# module.net
KiCad netlist of a schematic drawn in EAGLE
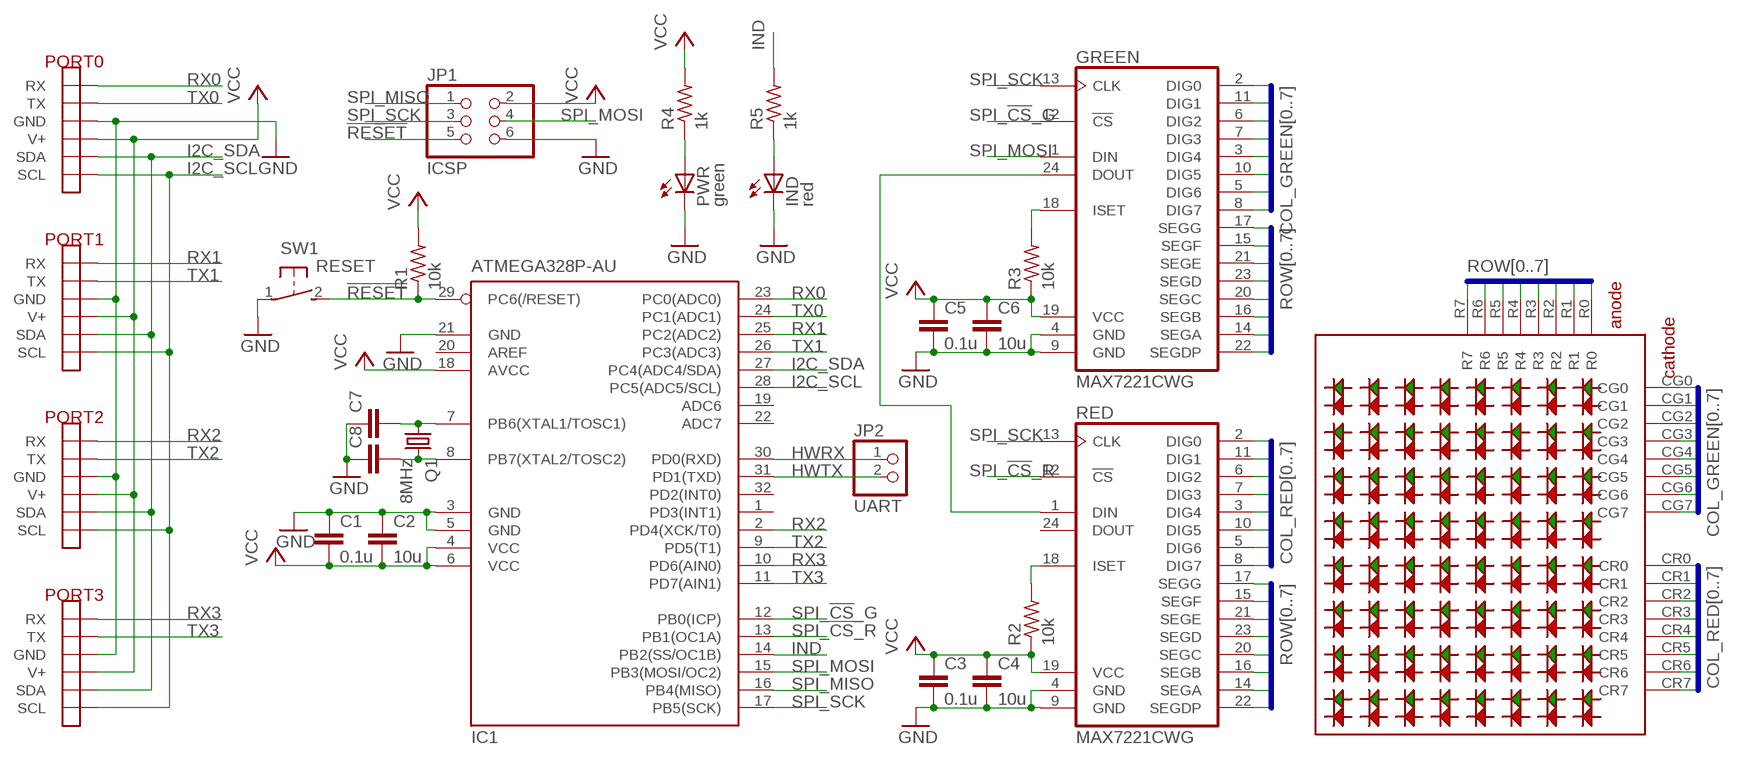
[diagram p0: schematic, sheet 1]

(export (version "E")
  (design (tool "Eeschema 10.0.6"))
  (components
    (comp (ref "C1")
      (value "0.1u")
      (footprint "eagle-import:C0805")
      (libsource (lib "eagle-import") (part "C-EUC0805"))
    )
    (comp (ref "C2")
      (value "10u")
      (footprint "eagle-import:C1206")
      (libsource (lib "eagle-import") (part "C-EUC1206"))
    )
    (comp (ref "C3")
      (value "0.1u")
      (footprint "eagle-import:C0805")
      (libsource (lib "eagle-import") (part "C-EUC0805"))
    )
    (comp (ref "C4")
      (value "10u")
      (footprint "eagle-import:C1206")
      (libsource (lib "eagle-import") (part "C-EUC1206"))
    )
    (comp (ref "C5")
      (value "0.1u")
      (footprint "eagle-import:C0805")
      (libsource (lib "eagle-import") (part "C-EUC0805"))
    )
    (comp (ref "C6")
      (value "10u")
      (footprint "eagle-import:C1206")
      (libsource (lib "eagle-import") (part "C-EUC1206"))
    )
    (comp (ref "C7")
      (value "C-EUC0805")
      (footprint "eagle-import:C0805")
      (libsource (lib "eagle-import") (part "C-EUC0805"))
    )
    (comp (ref "C8")
      (value "C-EUC0805")
      (footprint "eagle-import:C0805")
      (libsource (lib "eagle-import") (part "C-EUC0805"))
    )
    (comp (ref "GREEN")
      (value "MAX7221CWG")
      (footprint "eagle-import:SO24L")
      (fields (field (name "MF") "MAXIM"))
      (libsource (lib "eagle-import") (part "MAX7221CWG"))
    )
    (comp (ref "IC1")
      (value "ATMEGA328P-AU")
      (footprint "eagle-import:TQFP32-08")
      (fields (field (name "MF") "ATMEL"))
      (libsource (lib "eagle-import") (part "ATMEGA328P-AU"))
    )
    (comp (ref "IND")
      (value "red")
      (footprint "eagle-import:CHIPLED_0805")
      (libsource (lib "eagle-import") (part "LEDCHIPLED_0805"))
    )
    (comp (ref "JP1")
      (value "ICSP")
      (footprint "eagle-import:2X03")
      (libsource (lib "eagle-import") (part "PINHD-2X3"))
    )
    (comp (ref "JP2")
      (value "UART")
      (footprint "eagle-import:1X02")
      (libsource (lib "eagle-import") (part "PINHD-1X2"))
    )
    (comp (ref "PORT0")
      (value "PORT")
      (footprint "eagle-import:PORT")
      (libsource (lib "eagle-import") (part "PORT"))
    )
    (comp (ref "PORT1")
      (value "PORT")
      (footprint "eagle-import:PORT")
      (libsource (lib "eagle-import") (part "PORT"))
    )
    (comp (ref "PORT2")
      (value "PORT")
      (footprint "eagle-import:PORT")
      (libsource (lib "eagle-import") (part "PORT"))
    )
    (comp (ref "PORT3")
      (value "PORT")
      (footprint "eagle-import:PORT")
      (libsource (lib "eagle-import") (part "PORT"))
    )
    (comp (ref "PWR")
      (value "green")
      (footprint "eagle-import:CHIPLED_0805")
      (libsource (lib "eagle-import") (part "LEDCHIPLED_0805"))
    )
    (comp (ref "Q1")
      (value "8MHz")
      (footprint "eagle-import:HC49UP")
      (libsource (lib "eagle-import") (part "CRYSTALHC49UP"))
    )
    (comp (ref "R1")
      (value "10k")
      (footprint "eagle-import:R0805")
      (libsource (lib "eagle-import") (part "R-US_R0805"))
    )
    (comp (ref "R2")
      (value "10k")
      (footprint "eagle-import:R0805")
      (libsource (lib "eagle-import") (part "R-US_R0805"))
    )
    (comp (ref "R3")
      (value "10k")
      (footprint "eagle-import:R0805")
      (libsource (lib "eagle-import") (part "R-US_R0805"))
    )
    (comp (ref "R4")
      (value "1k")
      (footprint "eagle-import:R0805")
      (libsource (lib "eagle-import") (part "R-US_R0805"))
    )
    (comp (ref "R5")
      (value "1k")
      (footprint "eagle-import:R0805")
      (libsource (lib "eagle-import") (part "R-US_R0805"))
    )
    (comp (ref "RED")
      (value "MAX7221CWG")
      (footprint "eagle-import:SO24L")
      (fields (field (name "MF") "MAXIM"))
      (libsource (lib "eagle-import") (part "MAX7221CWG"))
    )
    (comp (ref "SW1")
      (value "RESET")
      (footprint "eagle-import:DTSM-3")
      (libsource (lib "eagle-import") (part "DTSM-3"))
    )
    (comp (ref "U$2")
      (value "88LED_MATRIX_BICOLOR_ROW_ANODE")
      (footprint "eagle-import:8_8LED_MATRIX_BICOLOR_ROW_ANODE")
      (libsource (lib "eagle-import") (part "88LED_MATRIX_BICOLOR_ROW_ANODE"))
    )
  )
  (nets
    (net (code "1") (name "/COL_GREEN0") (class "Default")
      (node (ref "GREEN") (pin "2") (pinfunction "DIG0_2") (pintype "output"))
      (node (ref "U$2") (pin "CG0") (pinfunction "CG0_CG0") (pintype "input"))
    )
    (net (code "2") (name "/COL_GREEN1") (class "Default")
      (node (ref "GREEN") (pin "11") (pinfunction "DIG1_11") (pintype "output"))
      (node (ref "U$2") (pin "CG1") (pinfunction "CG1_CG1") (pintype "input"))
    )
    (net (code "3") (name "/COL_GREEN2") (class "Default")
      (node (ref "GREEN") (pin "6") (pinfunction "DIG2_6") (pintype "output"))
      (node (ref "U$2") (pin "CG2") (pinfunction "CG2_CG2") (pintype "input"))
    )
    (net (code "4") (name "/COL_GREEN3") (class "Default")
      (node (ref "GREEN") (pin "7") (pinfunction "DIG3_7") (pintype "output"))
      (node (ref "U$2") (pin "CG3") (pinfunction "CG3_CG3") (pintype "input"))
    )
    (net (code "5") (name "/COL_GREEN4") (class "Default")
      (node (ref "GREEN") (pin "3") (pinfunction "DIG4_3") (pintype "output"))
      (node (ref "U$2") (pin "CG4") (pinfunction "CG4_CG4") (pintype "input"))
    )
    (net (code "6") (name "/COL_GREEN5") (class "Default")
      (node (ref "GREEN") (pin "10") (pinfunction "DIG5_10") (pintype "output"))
      (node (ref "U$2") (pin "CG5") (pinfunction "CG5_CG5") (pintype "input"))
    )
    (net (code "7") (name "/COL_GREEN6") (class "Default")
      (node (ref "GREEN") (pin "5") (pinfunction "DIG6_5") (pintype "output"))
      (node (ref "U$2") (pin "CG6") (pinfunction "CG6_CG6") (pintype "input"))
    )
    (net (code "8") (name "/COL_GREEN7") (class "Default")
      (node (ref "GREEN") (pin "8") (pinfunction "DIG7_8") (pintype "output"))
      (node (ref "U$2") (pin "CG7") (pinfunction "CG7_CG7") (pintype "input"))
    )
    (net (code "9") (name "/COL_RED0") (class "Default")
      (node (ref "RED") (pin "2") (pinfunction "DIG0_2") (pintype "output"))
      (node (ref "U$2") (pin "CR0") (pinfunction "CR0_CR0") (pintype "input"))
    )
    (net (code "10") (name "/COL_RED1") (class "Default")
      (node (ref "RED") (pin "11") (pinfunction "DIG1_11") (pintype "output"))
      (node (ref "U$2") (pin "CR1") (pinfunction "CR1_CR1") (pintype "input"))
    )
    (net (code "11") (name "/COL_RED2") (class "Default")
      (node (ref "RED") (pin "6") (pinfunction "DIG2_6") (pintype "output"))
      (node (ref "U$2") (pin "CR2") (pinfunction "CR2_CR2") (pintype "input"))
    )
    (net (code "12") (name "/COL_RED3") (class "Default")
      (node (ref "RED") (pin "7") (pinfunction "DIG3_7") (pintype "output"))
      (node (ref "U$2") (pin "CR3") (pinfunction "CR3_CR3") (pintype "input"))
    )
    (net (code "13") (name "/COL_RED4") (class "Default")
      (node (ref "RED") (pin "3") (pinfunction "DIG4_3") (pintype "output"))
      (node (ref "U$2") (pin "CR4") (pinfunction "CR4_CR4") (pintype "input"))
    )
    (net (code "14") (name "/COL_RED5") (class "Default")
      (node (ref "RED") (pin "10") (pinfunction "DIG5_10") (pintype "output"))
      (node (ref "U$2") (pin "CR5") (pinfunction "CR5_CR5") (pintype "input"))
    )
    (net (code "15") (name "/COL_RED6") (class "Default")
      (node (ref "RED") (pin "5") (pinfunction "DIG6_5") (pintype "output"))
      (node (ref "U$2") (pin "CR6") (pinfunction "CR6_CR6") (pintype "input"))
    )
    (net (code "16") (name "/COL_RED7") (class "Default")
      (node (ref "RED") (pin "8") (pinfunction "DIG7_8") (pintype "output"))
      (node (ref "U$2") (pin "CR7") (pinfunction "CR7_CR7") (pintype "input"))
    )
    (net (code "17") (name "/HWRX") (class "Default")
      (node (ref "IC1") (pin "30") (pinfunction "PD0(RXD)_30") (pintype "bidirectional"))
      (node (ref "JP2") (pin "1") (pinfunction "1_1") (pintype "passive"))
    )
    (net (code "18") (name "/HWTX") (class "Default")
      (node (ref "IC1") (pin "31") (pinfunction "PD1(TXD)_31") (pintype "bidirectional"))
      (node (ref "JP2") (pin "2") (pinfunction "2_2") (pintype "passive"))
    )
    (net (code "19") (name "/I2C_SCL") (class "Default")
      (node (ref "IC1") (pin "28") (pinfunction "PC5(ADC5/SCL)_28") (pintype "bidirectional"))
      (node (ref "PORT0") (pin "SCL_L") (pinfunction "SCL_SCL_L") (pintype "bidirectional"))
      (node (ref "PORT0") (pin "SCL_L_D") (pinfunction "SCL_SCL_L_D") (pintype "bidirectional"))
      (node (ref "PORT0") (pin "SCL_R") (pinfunction "SCL_SCL_R") (pintype "bidirectional"))
      (node (ref "PORT0") (pin "SCL_R_D") (pinfunction "SCL_SCL_R_D") (pintype "bidirectional"))
      (node (ref "PORT1") (pin "SCL_L") (pinfunction "SCL_SCL_L") (pintype "bidirectional"))
      (node (ref "PORT1") (pin "SCL_L_D") (pinfunction "SCL_SCL_L_D") (pintype "bidirectional"))
      (node (ref "PORT1") (pin "SCL_R") (pinfunction "SCL_SCL_R") (pintype "bidirectional"))
      (node (ref "PORT1") (pin "SCL_R_D") (pinfunction "SCL_SCL_R_D") (pintype "bidirectional"))
      (node (ref "PORT2") (pin "SCL_L") (pinfunction "SCL_SCL_L") (pintype "bidirectional"))
      (node (ref "PORT2") (pin "SCL_L_D") (pinfunction "SCL_SCL_L_D") (pintype "bidirectional"))
      (node (ref "PORT2") (pin "SCL_R") (pinfunction "SCL_SCL_R") (pintype "bidirectional"))
      (node (ref "PORT2") (pin "SCL_R_D") (pinfunction "SCL_SCL_R_D") (pintype "bidirectional"))
      (node (ref "PORT3") (pin "SCL_L") (pinfunction "SCL_SCL_L") (pintype "bidirectional"))
      (node (ref "PORT3") (pin "SCL_L_D") (pinfunction "SCL_SCL_L_D") (pintype "bidirectional"))
      (node (ref "PORT3") (pin "SCL_R") (pinfunction "SCL_SCL_R") (pintype "bidirectional"))
      (node (ref "PORT3") (pin "SCL_R_D") (pinfunction "SCL_SCL_R_D") (pintype "bidirectional"))
    )
    (net (code "20") (name "/I2C_SDA") (class "Default")
      (node (ref "IC1") (pin "27") (pinfunction "PC4(ADC4/SDA)_27") (pintype "bidirectional"))
      (node (ref "PORT0") (pin "SDA_L") (pinfunction "SDA_SDA_L") (pintype "bidirectional"))
      (node (ref "PORT0") (pin "SDA_L_D") (pinfunction "SDA_SDA_L_D") (pintype "bidirectional"))
      (node (ref "PORT0") (pin "SDA_R") (pinfunction "SDA_SDA_R") (pintype "bidirectional"))
      (node (ref "PORT0") (pin "SDA_R_D") (pinfunction "SDA_SDA_R_D") (pintype "bidirectional"))
      (node (ref "PORT1") (pin "SDA_L") (pinfunction "SDA_SDA_L") (pintype "bidirectional"))
      (node (ref "PORT1") (pin "SDA_L_D") (pinfunction "SDA_SDA_L_D") (pintype "bidirectional"))
      (node (ref "PORT1") (pin "SDA_R") (pinfunction "SDA_SDA_R") (pintype "bidirectional"))
      (node (ref "PORT1") (pin "SDA_R_D") (pinfunction "SDA_SDA_R_D") (pintype "bidirectional"))
      (node (ref "PORT2") (pin "SDA_L") (pinfunction "SDA_SDA_L") (pintype "bidirectional"))
      (node (ref "PORT2") (pin "SDA_L_D") (pinfunction "SDA_SDA_L_D") (pintype "bidirectional"))
      (node (ref "PORT2") (pin "SDA_R") (pinfunction "SDA_SDA_R") (pintype "bidirectional"))
      (node (ref "PORT2") (pin "SDA_R_D") (pinfunction "SDA_SDA_R_D") (pintype "bidirectional"))
      (node (ref "PORT3") (pin "SDA_L") (pinfunction "SDA_SDA_L") (pintype "bidirectional"))
      (node (ref "PORT3") (pin "SDA_L_D") (pinfunction "SDA_SDA_L_D") (pintype "bidirectional"))
      (node (ref "PORT3") (pin "SDA_R") (pinfunction "SDA_SDA_R") (pintype "bidirectional"))
      (node (ref "PORT3") (pin "SDA_R_D") (pinfunction "SDA_SDA_R_D") (pintype "bidirectional"))
    )
    (net (code "21") (name "/IND") (class "Default")
      (node (ref "IC1") (pin "14") (pinfunction "PB2(SS/OC1B)_14") (pintype "bidirectional"))
      (node (ref "R5") (pin "2") (pinfunction "2_2") (pintype "passive"))
    )
    (net (code "22") (name "/ROW0") (class "Default")
      (node (ref "GREEN") (pin "17") (pinfunction "SEGG_17") (pintype "output"))
      (node (ref "RED") (pin "17") (pinfunction "SEGG_17") (pintype "output"))
      (node (ref "U$2") (pin "R0") (pinfunction "R0_R0") (pintype "input"))
    )
    (net (code "23") (name "/ROW1") (class "Default")
      (node (ref "GREEN") (pin "15") (pinfunction "SEGF_15") (pintype "output"))
      (node (ref "RED") (pin "15") (pinfunction "SEGF_15") (pintype "output"))
      (node (ref "U$2") (pin "R1") (pinfunction "R1_R1") (pintype "input"))
    )
    (net (code "24") (name "/ROW2") (class "Default")
      (node (ref "GREEN") (pin "21") (pinfunction "SEGE_21") (pintype "output"))
      (node (ref "RED") (pin "21") (pinfunction "SEGE_21") (pintype "output"))
      (node (ref "U$2") (pin "R2") (pinfunction "R2_R2") (pintype "input"))
    )
    (net (code "25") (name "/ROW3") (class "Default")
      (node (ref "GREEN") (pin "23") (pinfunction "SEGD_23") (pintype "output"))
      (node (ref "RED") (pin "23") (pinfunction "SEGD_23") (pintype "output"))
      (node (ref "U$2") (pin "R3") (pinfunction "R3_R3") (pintype "input"))
    )
    (net (code "26") (name "/ROW4") (class "Default")
      (node (ref "GREEN") (pin "20") (pinfunction "SEGC_20") (pintype "output"))
      (node (ref "RED") (pin "20") (pinfunction "SEGC_20") (pintype "output"))
      (node (ref "U$2") (pin "R4") (pinfunction "R4_R4") (pintype "input"))
    )
    (net (code "27") (name "/ROW5") (class "Default")
      (node (ref "GREEN") (pin "16") (pinfunction "SEGB_16") (pintype "output"))
      (node (ref "RED") (pin "16") (pinfunction "SEGB_16") (pintype "output"))
      (node (ref "U$2") (pin "R5") (pinfunction "R5_R5") (pintype "input"))
    )
    (net (code "28") (name "/ROW6") (class "Default")
      (node (ref "GREEN") (pin "14") (pinfunction "SEGA_14") (pintype "output"))
      (node (ref "RED") (pin "14") (pinfunction "SEGA_14") (pintype "output"))
      (node (ref "U$2") (pin "R6") (pinfunction "R6_R6") (pintype "input"))
    )
    (net (code "29") (name "/ROW7") (class "Default")
      (node (ref "GREEN") (pin "22") (pinfunction "SEGDP_22") (pintype "output"))
      (node (ref "RED") (pin "22") (pinfunction "SEGDP_22") (pintype "output"))
      (node (ref "U$2") (pin "R7") (pinfunction "R7_R7") (pintype "input"))
    )
    (net (code "31") (name "/RX0") (class "Default")
      (node (ref "IC1") (pin "23") (pinfunction "PC0(ADC0)_23") (pintype "bidirectional"))
      (node (ref "PORT0") (pin "RX_L") (pinfunction "RX_RX_L") (pintype "input"))
      (node (ref "PORT0") (pin "RX_L_D") (pinfunction "RX_RX_L_D") (pintype "input"))
    )
    (net (code "32") (name "/RX1") (class "Default")
      (node (ref "IC1") (pin "25") (pinfunction "PC2(ADC2)_25") (pintype "bidirectional"))
      (node (ref "PORT1") (pin "RX_L") (pinfunction "RX_RX_L") (pintype "input"))
      (node (ref "PORT1") (pin "RX_L_D") (pinfunction "RX_RX_L_D") (pintype "input"))
    )
    (net (code "33") (name "/RX2") (class "Default")
      (node (ref "IC1") (pin "2") (pinfunction "PD4(XCK/T0)_2") (pintype "bidirectional"))
      (node (ref "PORT2") (pin "RX_L") (pinfunction "RX_RX_L") (pintype "input"))
      (node (ref "PORT2") (pin "RX_L_D") (pinfunction "RX_RX_L_D") (pintype "input"))
    )
    (net (code "34") (name "/RX3") (class "Default")
      (node (ref "IC1") (pin "10") (pinfunction "PD6(AIN0)_10") (pintype "bidirectional"))
      (node (ref "PORT3") (pin "RX_L") (pinfunction "RX_RX_L") (pintype "input"))
      (node (ref "PORT3") (pin "RX_L_D") (pinfunction "RX_RX_L_D") (pintype "input"))
    )
    (net (code "35") (name "/SPI_MISO") (class "Default")
      (node (ref "IC1") (pin "16") (pinfunction "PB4(MISO)_16") (pintype "bidirectional"))
      (node (ref "JP1") (pin "1") (pinfunction "1_1") (pintype "passive"))
    )
    (net (code "36") (name "/SPI_MOSI") (class "Default")
      (node (ref "GREEN") (pin "1") (pinfunction "DIN_1") (pintype "input"))
      (node (ref "IC1") (pin "15") (pinfunction "PB3(MOSI/OC2)_15") (pintype "bidirectional"))
      (node (ref "JP1") (pin "4") (pinfunction "4_4") (pintype "passive"))
    )
    (net (code "37") (name "/SPI_SCK") (class "Default")
      (node (ref "GREEN") (pin "13") (pinfunction "CLK_13") (pintype "input"))
      (node (ref "IC1") (pin "17") (pinfunction "PB5(SCK)_17") (pintype "bidirectional"))
      (node (ref "JP1") (pin "3") (pinfunction "3_3") (pintype "passive"))
      (node (ref "RED") (pin "13") (pinfunction "CLK_13") (pintype "input"))
    )
    (net (code "38") (name "/SPI_~{CS}_G") (class "Default")
      (node (ref "GREEN") (pin "12") (pinfunction "~{CS}_12") (pintype "input"))
      (node (ref "IC1") (pin "12") (pinfunction "PB0(ICP)_12") (pintype "bidirectional"))
    )
    (net (code "39") (name "/SPI_~{CS}_R") (class "Default")
      (node (ref "IC1") (pin "13") (pinfunction "PB1(OC1A)_13") (pintype "bidirectional"))
      (node (ref "RED") (pin "12") (pinfunction "~{CS}_12") (pintype "input"))
    )
    (net (code "40") (name "/TX0") (class "Default")
      (node (ref "IC1") (pin "24") (pinfunction "PC1(ADC1)_24") (pintype "bidirectional"))
      (node (ref "PORT0") (pin "TX_R") (pinfunction "TX_TX_R") (pintype "output"))
      (node (ref "PORT0") (pin "TX_R_D") (pinfunction "TX_TX_R_D") (pintype "output"))
    )
    (net (code "41") (name "/TX1") (class "Default")
      (node (ref "IC1") (pin "26") (pinfunction "PC3(ADC3)_26") (pintype "bidirectional"))
      (node (ref "PORT1") (pin "TX_R") (pinfunction "TX_TX_R") (pintype "output"))
      (node (ref "PORT1") (pin "TX_R_D") (pinfunction "TX_TX_R_D") (pintype "output"))
    )
    (net (code "42") (name "/TX2") (class "Default")
      (node (ref "IC1") (pin "9") (pinfunction "PD5(T1)_9") (pintype "bidirectional"))
      (node (ref "PORT2") (pin "TX_R") (pinfunction "TX_TX_R") (pintype "output"))
      (node (ref "PORT2") (pin "TX_R_D") (pinfunction "TX_TX_R_D") (pintype "output"))
    )
    (net (code "43") (name "/TX3") (class "Default")
      (node (ref "IC1") (pin "11") (pinfunction "PD7(AIN1)_11") (pintype "bidirectional"))
      (node (ref "PORT3") (pin "TX_R") (pinfunction "TX_TX_R") (pintype "output"))
      (node (ref "PORT3") (pin "TX_R_D") (pinfunction "TX_TX_R_D") (pintype "output"))
    )
    (net (code "44") (name "/~{RESET}") (class "Default")
      (node (ref "IC1") (pin "29") (pinfunction "PC6(/RESET)_29") (pintype "bidirectional"))
      (node (ref "JP1") (pin "5") (pinfunction "5_5") (pintype "passive"))
      (node (ref "R1") (pin "1") (pinfunction "1_1") (pintype "passive"))
      (node (ref "SW1") (pin "2") (pinfunction "2_2") (pintype "passive"))
    )
    (net (code "45") (name "GND") (class "Default")
      (node (ref "C1") (pin "1") (pinfunction "1_1") (pintype "passive"))
      (node (ref "C2") (pin "1") (pinfunction "1_1") (pintype "passive"))
      (node (ref "C3") (pin "2") (pinfunction "2_2") (pintype "passive"))
      (node (ref "C4") (pin "2") (pinfunction "2_2") (pintype "passive"))
      (node (ref "C5") (pin "2") (pinfunction "2_2") (pintype "passive"))
      (node (ref "C6") (pin "2") (pinfunction "2_2") (pintype "passive"))
      (node (ref "C7") (pin "1") (pinfunction "1_1") (pintype "passive"))
      (node (ref "C8") (pin "1") (pinfunction "1_1") (pintype "passive"))
      (node (ref "GREEN") (pin "4") (pinfunction "GND_4") (pintype "power_in"))
      (node (ref "GREEN") (pin "9") (pinfunction "GND_9") (pintype "power_in"))
      (node (ref "IC1") (pin "21") (pinfunction "GND_21") (pintype "power_in"))
      (node (ref "IC1") (pin "3") (pinfunction "GND_3") (pintype "power_in"))
      (node (ref "IC1") (pin "5") (pinfunction "GND_5") (pintype "power_in"))
      (node (ref "IND") (pin "C") (pinfunction "C_C") (pintype "passive"))
      (node (ref "JP1") (pin "6") (pinfunction "6_6") (pintype "passive"))
      (node (ref "PORT0") (pin "GND_L") (pinfunction "GND_GND_L") (pintype "power_in"))
      (node (ref "PORT0") (pin "GND_L_D") (pinfunction "GND_GND_L_D") (pintype "power_in"))
      (node (ref "PORT0") (pin "GND_R") (pinfunction "GND_GND_R") (pintype "power_in"))
      (node (ref "PORT0") (pin "GND_R_D") (pinfunction "GND_GND_R_D") (pintype "power_in"))
      (node (ref "PORT1") (pin "GND_L") (pinfunction "GND_GND_L") (pintype "power_in"))
      (node (ref "PORT1") (pin "GND_L_D") (pinfunction "GND_GND_L_D") (pintype "power_in"))
      (node (ref "PORT1") (pin "GND_R") (pinfunction "GND_GND_R") (pintype "power_in"))
      (node (ref "PORT1") (pin "GND_R_D") (pinfunction "GND_GND_R_D") (pintype "power_in"))
      (node (ref "PORT2") (pin "GND_L") (pinfunction "GND_GND_L") (pintype "power_in"))
      (node (ref "PORT2") (pin "GND_L_D") (pinfunction "GND_GND_L_D") (pintype "power_in"))
      (node (ref "PORT2") (pin "GND_R") (pinfunction "GND_GND_R") (pintype "power_in"))
      (node (ref "PORT2") (pin "GND_R_D") (pinfunction "GND_GND_R_D") (pintype "power_in"))
      (node (ref "PORT3") (pin "GND_L") (pinfunction "GND_GND_L") (pintype "power_in"))
      (node (ref "PORT3") (pin "GND_L_D") (pinfunction "GND_GND_L_D") (pintype "power_in"))
      (node (ref "PORT3") (pin "GND_R") (pinfunction "GND_GND_R") (pintype "power_in"))
      (node (ref "PORT3") (pin "GND_R_D") (pinfunction "GND_GND_R_D") (pintype "power_in"))
      (node (ref "PWR") (pin "C") (pinfunction "C_C") (pintype "passive"))
      (node (ref "RED") (pin "4") (pinfunction "GND_4") (pintype "power_in"))
      (node (ref "RED") (pin "9") (pinfunction "GND_9") (pintype "power_in"))
      (node (ref "SW1") (pin "1") (pinfunction "1_1") (pintype "passive"))
    )
    (net (code "46") (name "Net-(GREEN-DOUT)") (class "Default")
      (node (ref "GREEN") (pin "24") (pinfunction "DOUT_24") (pintype "output"))
      (node (ref "RED") (pin "1") (pinfunction "DIN_1") (pintype "input"))
    )
    (net (code "47") (name "Net-(GREEN-ISET)") (class "Default")
      (node (ref "GREEN") (pin "18") (pinfunction "ISET_18") (pintype "input"))
      (node (ref "R3") (pin "2") (pinfunction "2_2") (pintype "passive"))
    )
    (net (code "48") (name "Net-(IC1-PB6(XTAL1{slash}TOSC1))") (class "Default")
      (node (ref "C7") (pin "2") (pinfunction "2_2") (pintype "passive"))
      (node (ref "IC1") (pin "7") (pinfunction "PB6(XTAL1/TOSC1)_7") (pintype "bidirectional"))
      (node (ref "Q1") (pin "1") (pinfunction "1_1") (pintype "passive"))
    )
    (net (code "49") (name "Net-(IC1-PB7(XTAL2{slash}TOSC2))") (class "Default")
      (node (ref "C8") (pin "2") (pinfunction "2_2") (pintype "passive"))
      (node (ref "IC1") (pin "8") (pinfunction "PB7(XTAL2/TOSC2)_8") (pintype "bidirectional"))
      (node (ref "Q1") (pin "2") (pinfunction "2_2") (pintype "passive"))
    )
    (net (code "50") (name "Net-(IND-PadA)") (class "Default")
      (node (ref "IND") (pin "A") (pinfunction "A_A") (pintype "passive"))
      (node (ref "R5") (pin "1") (pinfunction "1_1") (pintype "passive"))
    )
    (net (code "51") (name "Net-(PWR-PadA)") (class "Default")
      (node (ref "PWR") (pin "A") (pinfunction "A_A") (pintype "passive"))
      (node (ref "R4") (pin "1") (pinfunction "1_1") (pintype "passive"))
    )
    (net (code "52") (name "Net-(RED-ISET)") (class "Default")
      (node (ref "R2") (pin "2") (pinfunction "2_2") (pintype "passive"))
      (node (ref "RED") (pin "18") (pinfunction "ISET_18") (pintype "input"))
    )
    (net (code "53") (name "VCC") (class "Default")
      (node (ref "C1") (pin "2") (pinfunction "2_2") (pintype "passive"))
      (node (ref "C2") (pin "2") (pinfunction "2_2") (pintype "passive"))
      (node (ref "C3") (pin "1") (pinfunction "1_1") (pintype "passive"))
      (node (ref "C4") (pin "1") (pinfunction "1_1") (pintype "passive"))
      (node (ref "C5") (pin "1") (pinfunction "1_1") (pintype "passive"))
      (node (ref "C6") (pin "1") (pinfunction "1_1") (pintype "passive"))
      (node (ref "GREEN") (pin "19") (pinfunction "VCC_19") (pintype "power_in"))
      (node (ref "IC1") (pin "18") (pinfunction "AVCC_18") (pintype "power_in"))
      (node (ref "IC1") (pin "4") (pinfunction "VCC_4") (pintype "power_in"))
      (node (ref "IC1") (pin "6") (pinfunction "VCC_6") (pintype "power_in"))
      (node (ref "JP1") (pin "2") (pinfunction "2_2") (pintype "passive"))
      (node (ref "PORT0") (pin "V+_L") (pinfunction "V+_V+_L") (pintype "power_in"))
      (node (ref "PORT0") (pin "V+_L_D") (pinfunction "V+_V+_L_D") (pintype "power_in"))
      (node (ref "PORT0") (pin "V+_R") (pinfunction "V+_V+_R") (pintype "power_in"))
      (node (ref "PORT0") (pin "V+_R_D") (pinfunction "V+_V+_R_D") (pintype "power_in"))
      (node (ref "PORT1") (pin "V+_L") (pinfunction "V+_V+_L") (pintype "power_in"))
      (node (ref "PORT1") (pin "V+_L_D") (pinfunction "V+_V+_L_D") (pintype "power_in"))
      (node (ref "PORT1") (pin "V+_R") (pinfunction "V+_V+_R") (pintype "power_in"))
      (node (ref "PORT1") (pin "V+_R_D") (pinfunction "V+_V+_R_D") (pintype "power_in"))
      (node (ref "PORT2") (pin "V+_L") (pinfunction "V+_V+_L") (pintype "power_in"))
      (node (ref "PORT2") (pin "V+_L_D") (pinfunction "V+_V+_L_D") (pintype "power_in"))
      (node (ref "PORT2") (pin "V+_R") (pinfunction "V+_V+_R") (pintype "power_in"))
      (node (ref "PORT2") (pin "V+_R_D") (pinfunction "V+_V+_R_D") (pintype "power_in"))
      (node (ref "PORT3") (pin "V+_L") (pinfunction "V+_V+_L") (pintype "power_in"))
      (node (ref "PORT3") (pin "V+_L_D") (pinfunction "V+_V+_L_D") (pintype "power_in"))
      (node (ref "PORT3") (pin "V+_R") (pinfunction "V+_V+_R") (pintype "power_in"))
      (node (ref "PORT3") (pin "V+_R_D") (pinfunction "V+_V+_R_D") (pintype "power_in"))
      (node (ref "R1") (pin "2") (pinfunction "2_2") (pintype "passive"))
      (node (ref "R2") (pin "1") (pinfunction "1_1") (pintype "passive"))
      (node (ref "R3") (pin "1") (pinfunction "1_1") (pintype "passive"))
      (node (ref "R4") (pin "2") (pinfunction "2_2") (pintype "passive"))
      (node (ref "RED") (pin "19") (pinfunction "VCC_19") (pintype "power_in"))
    )
    (net (code "54") (name "unconnected-(IC1-ADC6-Pad19)") (class "Default")
      (node (ref "IC1") (pin "19") (pinfunction "ADC6_19") (pintype "bidirectional"))
    )
    (net (code "55") (name "unconnected-(IC1-ADC7-Pad22)") (class "Default")
      (node (ref "IC1") (pin "22") (pinfunction "ADC7_22") (pintype "bidirectional"))
    )
    (net (code "56") (name "unconnected-(IC1-AREF-Pad20)") (class "Default")
      (node (ref "IC1") (pin "20") (pinfunction "AREF_20") (pintype "passive"))
    )
    (net (code "57") (name "unconnected-(IC1-PD2(INT0)-Pad32)") (class "Default")
      (node (ref "IC1") (pin "32") (pinfunction "PD2(INT0)_32") (pintype "bidirectional"))
    )
    (net (code "58") (name "unconnected-(IC1-PD3(INT1)-Pad1)") (class "Default")
      (node (ref "IC1") (pin "1") (pinfunction "PD3(INT1)_1") (pintype "bidirectional"))
    )
    (net (code "59") (name "unconnected-(RED-DOUT-Pad24)") (class "Default")
      (node (ref "RED") (pin "24") (pinfunction "DOUT_24") (pintype "output"))
    )
  )
)
